# Power_Subsystem.net
KiCad netlist of a schematic drawn in Altium Designer
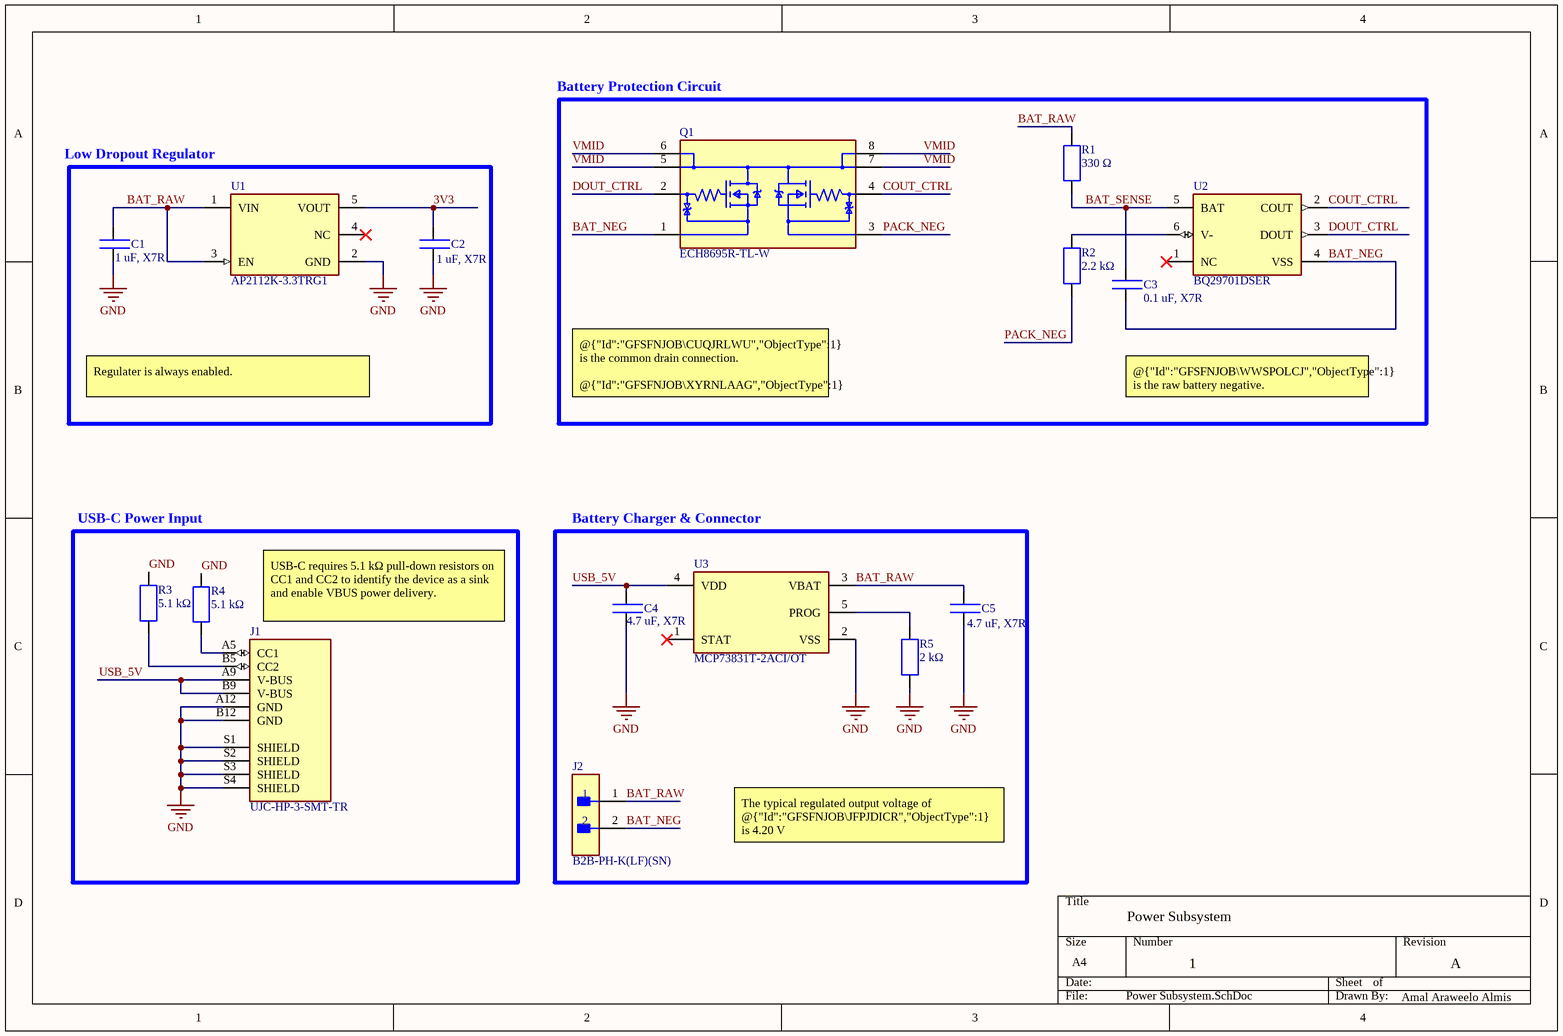
[diagram p0: Power Subsystem.SchDoc]

(export (version "E")
  (design (tool "Eeschema 10.0.6"))
  (components
    (comp (ref "C1")
      (value "1 uF, X7R")
      (footprint "CAP_0402")
      (description "Multilayer Ceramic Capacitors MLCC - SMD/SMT 6.3V 1uF X7R 0402 10% HI CV")
      (fields (field (name "LCSC PART NUMBER") "C106200") (field (name "TOLERANCE") "5%"))
      (libsource (lib "Generic-Schematic-Library") (part "CAP_0402"))
    )
    (comp (ref "C2")
      (value "1 uF, X7R")
      (footprint "CAP_0402")
      (description "Multilayer Ceramic Capacitors MLCC - SMD/SMT 6.3V 1uF X7R 0402 10% HI CV")
      (fields
        (field (name "MANUFACTURER") "YAGEO")
        (field (name "MANUFACTURER PART NUMBER") "CC0402JRNPO9BN101")
      )
      (libsource (lib "Generic-Schematic-Library") (part "CAP_0402"))
    )
    (comp (ref "C3")
      (value "0.1 uF, X7R")
      (footprint "CAP_0402")
      (description "Multilayer Ceramic Capacitors MLCC - SMD/SMT 16 V 0.1uF X7R 0402 10%")
      (fields (field (name "LCSC PART NUMBER") "C106200") (field (name "TOLERANCE") "5%"))
      (libsource (lib "Generic-Schematic-Library") (part "CAP_0402"))
    )
    (comp (ref "C4")
      (value "4.7 uF, X7R")
      (footprint "CAP_0402")
      (description "Multilayer Ceramic Capacitor MLCC")
      (fields (field (name "LCSC PART NUMBER") "C106200") (field (name "TOLERANCE") "5%"))
      (libsource (lib "Generic-Schematic-Library") (part "CAP_0402"))
    )
    (comp (ref "C5")
      (value "4.7 uF, X7R")
      (footprint "CAP_0402")
      (description "Multilayer Ceramic Capacitor MLCC")
      (fields
        (field (name "MANUFACTURER") "YAGEO")
        (field (name "MANUFACTURER PART NUMBER") "CC0402JRNPO9BN101")
      )
      (libsource (lib "Generic-Schematic-Library") (part "CAP_0402"))
    )
    (comp (ref "J1")
      (value "UJC-HP-3-SMT-TR")
      (footprint "CUI_UJC-HP-3-SMT-TR")
      (libsource (lib "Generic-Schematic-Library") (part "UJC-HP-3-SMT-TR"))
    )
    (comp (ref "J2")
      (value "B2B-PH-K(LF)(SN)")
      (footprint "FP-B2B-PH-K_LF_SN-MFG")
      (description "Connector Header Through Hole 2 position 0.079\" (2.00mm)")
      (libsource (lib "Generic-Schematic-Library") (part "CMP-17439-000674-1"))
    )
    (comp (ref "Q1")
      (value "ECH8695R-TL-W")
      (footprint "FP-318BF-MFG")
      (description "ECH8695R-TL-W Dual N-Channel Power MOSFET, 24V, 11 A, 9.1 mΩ")
      (libsource (lib "Generic-Schematic-Library") (part "CMP-00278-51167104-1"))
    )
    (comp (ref "R1")
      (value "330 Ω")
      (footprint "RES_0402")
      (description "Resistor SMD 0402 Generic")
      (fields (field (name "TOLERANCE") "1%") (field (name "LCSC PART NUMBER") "C93947"))
      (libsource (lib "Generic-Schematic-Library") (part "RES_0402"))
    )
    (comp (ref "R2")
      (value "2.2 kΩ")
      (footprint "RES_0402")
      (description "Resistor SMD 0402 Generic")
      (fields (field (name "TOLERANCE") "1%") (field (name "LCSC PART NUMBER") "C93947"))
      (libsource (lib "Generic-Schematic-Library") (part "RES_0402"))
    )
    (comp (ref "R3")
      (value "5.1 kΩ")
      (footprint "RES_0402")
      (description "Resistor SMD 0402 Generic")
      (fields (field (name "TOLERANCE") "1%") (field (name "LCSC PART NUMBER") "C93947"))
      (libsource (lib "Generic-Schematic-Library") (part "RES_0402"))
    )
    (comp (ref "R4")
      (value "5.1 kΩ")
      (footprint "RES_0402")
      (description "Resistor SMD 0402 Generic")
      (fields
        (field (name "MANUFACTURER") "YAGEO")
        (field (name "MANUFACTURER PART NUMBER") "RC0402FR07150KL")
      )
      (libsource (lib "Generic-Schematic-Library") (part "RES_0402"))
    )
    (comp (ref "R5")
      (value "2 kΩ")
      (footprint "RES_0402")
      (description "Resistor SMD 0402 Generic")
      (fields (field (name "TOLERANCE") "1%") (field (name "LCSC PART NUMBER") "C93947"))
      (libsource (lib "Generic-Schematic-Library") (part "RES_0402"))
    )
    (comp (ref "U1")
      (value "AP2112K-3.3TRG1")
      (footprint "FP-SOT25-IPC_C")
      (description "IC REG LINEAR 3.3V 600MA SOT25")
      (libsource (lib "Generic-Schematic-Library") (part "CMP-12756-000035-1"))
    )
    (comp (ref "U2")
      (value "BQ29701DSER")
      (footprint "FP-DSE0006A-IPC_A")
      (description "IC LITHIUM BATT PROTECT 6-SON")
      (libsource (lib "Generic-Schematic-Library") (part "CMP-04911-000034-1"))
    )
    (comp (ref "U3")
      (value "MCP73831T-2ACI/OT")
      (footprint "FP-C04-091-OT-IPC_A")
      (description "IC CONTROLLR LI-ION 4.2V SOT23-5")
      (libsource (lib "Generic-Schematic-Library") (part "CMP-0133-00143-2"))
    )
  )
  (nets
    (net (code "1") (name "/3V3") (class "Default")
      (node (ref "C2") (pin "2") (pinfunction "2_2") (pintype "passive"))
      (node (ref "U1") (pin "5") (pinfunction "VOUT_5") (pintype "power_in"))
    )
    (net (code "2") (name "/BAT_NEG") (class "Default")
      (node (ref "C3") (pin "1") (pinfunction "1_1") (pintype "passive"))
      (node (ref "J2") (pin "2") (pinfunction "2_2") (pintype "passive"))
      (node (ref "Q1") (pin "1") (pinfunction "Source1_1") (pintype "passive"))
      (node (ref "U2") (pin "4") (pinfunction "VSS_4") (pintype "power_in"))
    )
    (net (code "3") (name "/BAT_RAW") (class "Default")
      (node (ref "C1") (pin "2") (pinfunction "2_2") (pintype "passive"))
      (node (ref "C5") (pin "2") (pinfunction "2_2") (pintype "passive"))
      (node (ref "J2") (pin "1") (pinfunction "1_1") (pintype "passive"))
      (node (ref "R1") (pin "1") (pinfunction "1_1") (pintype "passive"))
      (node (ref "U1") (pin "1") (pinfunction "VIN_1") (pintype "power_in"))
      (node (ref "U1") (pin "3") (pinfunction "EN_3") (pintype "input"))
      (node (ref "U3") (pin "3") (pinfunction "VBAT_3") (pintype "power_in"))
    )
    (net (code "4") (name "/BAT_SENSE") (class "Default")
      (node (ref "C3") (pin "2") (pinfunction "2_2") (pintype "passive"))
      (node (ref "R1") (pin "2") (pinfunction "2_2") (pintype "passive"))
      (node (ref "U2") (pin "5") (pinfunction "BAT_5") (pintype "power_in"))
    )
    (net (code "5") (name "/COUT_CTRL") (class "Default")
      (node (ref "Q1") (pin "4") (pinfunction "Gate2_4") (pintype "passive"))
      (node (ref "U2") (pin "2") (pinfunction "COUT_2") (pintype "output"))
    )
    (net (code "6") (name "/DOUT_CTRL") (class "Default")
      (node (ref "Q1") (pin "2") (pinfunction "Gate1_2") (pintype "passive"))
      (node (ref "U2") (pin "3") (pinfunction "DOUT_3") (pintype "output"))
    )
    (net (code "7") (name "/PACK_NEG") (class "Default")
      (node (ref "Q1") (pin "3") (pinfunction "Source2_3") (pintype "passive"))
      (node (ref "R2") (pin "1") (pinfunction "1_1") (pintype "passive"))
    )
    (net (code "8") (name "/USB_5V") (class "Default")
      (node (ref "C4") (pin "2") (pinfunction "2_2") (pintype "passive"))
      (node (ref "J1") (pin "A9") (pinfunction "V-BUS_A9") (pintype "power_in"))
      (node (ref "J1") (pin "B9") (pinfunction "V-BUS_B9") (pintype "power_in"))
      (node (ref "U3") (pin "4") (pinfunction "VDD_4") (pintype "power_in"))
    )
    (net (code "9") (name "/VMID") (class "Default")
      (node (ref "Q1") (pin "5") (pinfunction "Drain_5") (pintype "passive"))
      (node (ref "Q1") (pin "6") (pinfunction "Drain_6") (pintype "passive"))
      (node (ref "Q1") (pin "7") (pinfunction "Drain_7") (pintype "passive"))
      (node (ref "Q1") (pin "8") (pinfunction "Drain_8") (pintype "passive"))
    )
    (net (code "10") (name "GND") (class "Default")
      (node (ref "C1") (pin "1") (pinfunction "1_1") (pintype "passive"))
      (node (ref "C2") (pin "1") (pinfunction "1_1") (pintype "passive"))
      (node (ref "C4") (pin "1") (pinfunction "1_1") (pintype "passive"))
      (node (ref "C5") (pin "1") (pinfunction "1_1") (pintype "passive"))
      (node (ref "J1") (pin "A12") (pinfunction "GND_A12") (pintype "power_in"))
      (node (ref "J1") (pin "B12") (pinfunction "GND_B12") (pintype "power_in"))
      (node (ref "J1") (pin "S1") (pinfunction "SHIELD_S1") (pintype "passive"))
      (node (ref "J1") (pin "S2") (pinfunction "SHIELD_S2") (pintype "passive"))
      (node (ref "J1") (pin "S3") (pinfunction "SHIELD_S3") (pintype "passive"))
      (node (ref "J1") (pin "S4") (pinfunction "SHIELD_S4") (pintype "passive"))
      (node (ref "R3") (pin "1") (pinfunction "1_1") (pintype "passive"))
      (node (ref "R4") (pin "2") (pinfunction "2_2") (pintype "passive"))
      (node (ref "R5") (pin "1") (pinfunction "1_1") (pintype "passive"))
      (node (ref "U1") (pin "2") (pinfunction "GND_2") (pintype "power_in"))
      (node (ref "U3") (pin "2") (pinfunction "VSS_2") (pintype "power_in"))
    )
    (net (code "11") (name "Net-(J1-CC1)") (class "Default")
      (node (ref "J1") (pin "A5") (pinfunction "CC1_A5") (pintype "bidirectional"))
      (node (ref "R4") (pin "1") (pinfunction "1_1") (pintype "passive"))
    )
    (net (code "12") (name "Net-(J1-CC2)") (class "Default")
      (node (ref "J1") (pin "B5") (pinfunction "CC2_B5") (pintype "bidirectional"))
      (node (ref "R3") (pin "2") (pinfunction "2_2") (pintype "passive"))
    )
    (net (code "13") (name "Net-(U2-V-)") (class "Default")
      (node (ref "R2") (pin "2") (pinfunction "2_2") (pintype "passive"))
      (node (ref "U2") (pin "6") (pinfunction "V-_6") (pintype "bidirectional"))
    )
    (net (code "14") (name "Net-(U3-PROG)") (class "Default")
      (node (ref "R5") (pin "2") (pinfunction "2_2") (pintype "passive"))
      (node (ref "U3") (pin "5") (pinfunction "PROG_5") (pintype "passive"))
    )
    (net (code "15") (name "unconnected-(U1-NC-Pad4)") (class "Default")
      (node (ref "U1") (pin "4") (pinfunction "NC_4") (pintype "passive+no_connect"))
    )
    (net (code "16") (name "unconnected-(U2-NC-Pad1)") (class "Default")
      (node (ref "U2") (pin "1") (pinfunction "NC_1") (pintype "passive+no_connect"))
    )
    (net (code "17") (name "unconnected-(U3-STAT-Pad1)") (class "Default")
      (node (ref "U3") (pin "1") (pinfunction "STAT_1") (pintype "passive+no_connect"))
    )
  )
)
